# fastic.net
KiCad netlist of a schematic drawn in Altium Designer
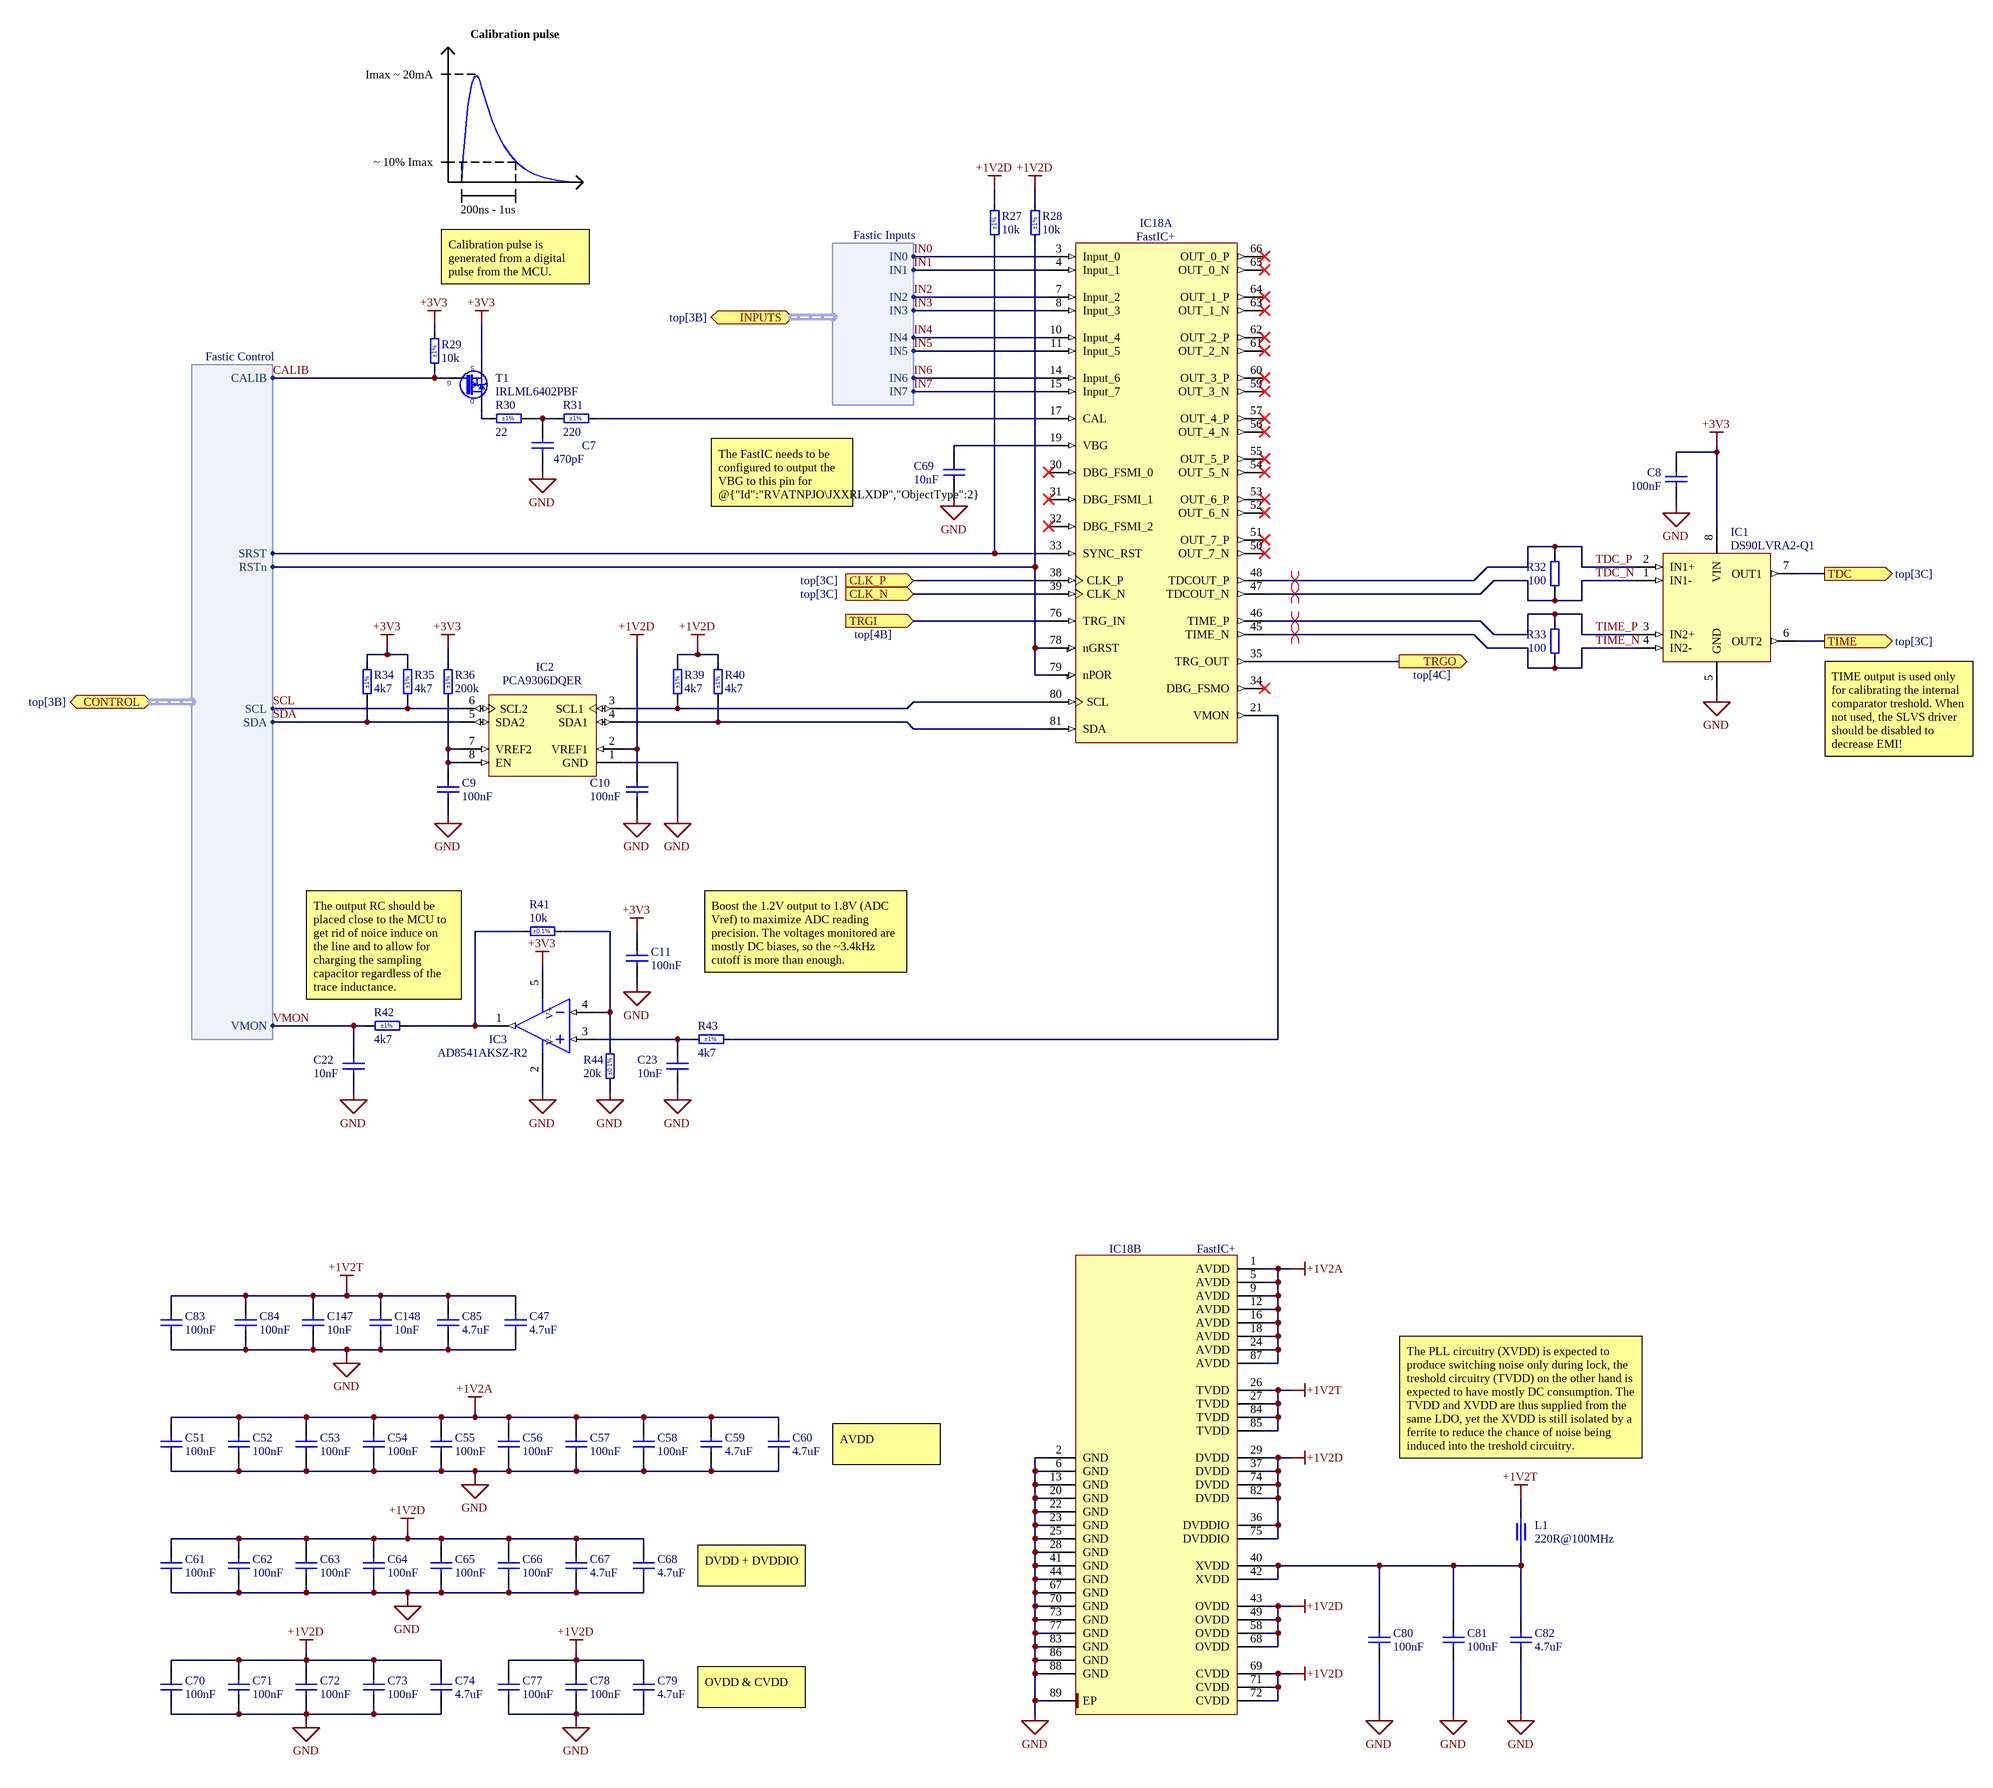
[diagram p0: fastic.SchDoc]

(export (version "E")
  (design (tool "Eeschema 10.0.6"))
  (components
    (comp (ref "C7")
      (value "470pF")
      (footprint "CAPC1005X55N")
      (description "Non-polarised capacitor")
      (fields
        (field (name "PART NUMBER") "CC0402_470PF_50V_10%_X7R")
        (field (name "VOLTAGE") "50V")
        (field (name "AUTHOR") "CERN DEM JLC")
      )
      (libsource (lib "Capacitors") (part "Capacitor - non polarized"))
    )
    (comp (ref "C8")
      (value "100nF")
      (footprint "CAPC1005X55N")
      (description "Non-polarised capacitor")
      (fields
        (field (name "PART NUMBER") "CC0402_100NF_16V_10%_X7R")
        (field (name "VOLTAGE") "16V")
        (field (name "AUTHOR") "CERN DEM JLC")
      )
      (libsource (lib "Capacitors") (part "Capacitor - non polarized"))
    )
    (comp (ref "C9")
      (value "100nF")
      (footprint "CAPC1005X55N")
      (description "Non-polarised capacitor")
      (fields
        (field (name "PART NUMBER") "CC0402_100NF_16V_10%_X7R")
        (field (name "VOLTAGE") "16V")
        (field (name "AUTHOR") "CERN DEM JLC")
      )
      (libsource (lib "Capacitors") (part "Capacitor - non polarized"))
    )
    (comp (ref "C10")
      (value "100nF")
      (footprint "CAPC1005X55N")
      (description "Non-polarised capacitor")
      (fields
        (field (name "PART NUMBER") "CC0402_100NF_16V_10%_X7R")
        (field (name "VOLTAGE") "16V")
        (field (name "AUTHOR") "CERN DEM JLC")
      )
      (libsource (lib "Capacitors") (part "Capacitor - non polarized"))
    )
    (comp (ref "C11")
      (value "100nF")
      (footprint "CAPC1005X55N")
      (description "Non-polarised capacitor")
      (fields
        (field (name "PART NUMBER") "CC0402_100NF_16V_10%_X7R")
        (field (name "VOLTAGE") "16V")
        (field (name "AUTHOR") "CERN DEM JLC")
      )
      (libsource (lib "Capacitors") (part "Capacitor - non polarized"))
    )
    (comp (ref "C22")
      (value "10nF")
      (footprint "CAPC1005X55N")
      (description "Non-polarised capacitor")
      (fields
        (field (name "PART NUMBER") "CC0402_10NF_50V_10%_X7R")
        (field (name "VOLTAGE") "50V")
        (field (name "AUTHOR") "CERN DEM MR")
      )
      (libsource (lib "Capacitors") (part "Capacitor - non polarized"))
    )
    (comp (ref "C23")
      (value "10nF")
      (footprint "CAPC1005X55N")
      (description "Non-polarised capacitor")
      (fields
        (field (name "PART NUMBER") "CC0402_10NF_50V_10%_X7R")
        (field (name "VOLTAGE") "50V")
        (field (name "AUTHOR") "CERN DEM MR")
      )
      (libsource (lib "Capacitors") (part "Capacitor - non polarized"))
    )
    (comp (ref "C47")
      (value "4.7uF")
      (footprint "CAPC1608X87N")
      (description "Non-polarised capacitor")
      (fields
        (field (name "PART NUMBER") "CC0603_4.7UF_6.3V_10%_X5R")
        (field (name "VOLTAGE") "6.3V")
        (field (name "AUTHOR") "CERN DEM JLC")
      )
      (libsource (lib "Capacitors") (part "Capacitor - non polarized"))
    )
    (comp (ref "C51")
      (value "100nF")
      (footprint "CAPC1005X55N")
      (description "Non-polarised capacitor")
      (fields
        (field (name "PART NUMBER") "CC0402_100NF_16V_10%_X7R")
        (field (name "VOLTAGE") "16V")
        (field (name "AUTHOR") "CERN DEM JLC")
      )
      (libsource (lib "Capacitors") (part "Capacitor - non polarized"))
    )
    (comp (ref "C52")
      (value "100nF")
      (footprint "CAPC1005X55N")
      (description "Non-polarised capacitor")
      (fields
        (field (name "PART NUMBER") "CC0402_100NF_16V_10%_X7R")
        (field (name "VOLTAGE") "16V")
        (field (name "AUTHOR") "CERN DEM JLC")
      )
      (libsource (lib "Capacitors") (part "Capacitor - non polarized"))
    )
    (comp (ref "C53")
      (value "100nF")
      (footprint "CAPC1005X55N")
      (description "Non-polarised capacitor")
      (fields
        (field (name "PART NUMBER") "CC0402_100NF_16V_10%_X7R")
        (field (name "VOLTAGE") "16V")
        (field (name "AUTHOR") "CERN DEM JLC")
      )
      (libsource (lib "Capacitors") (part "Capacitor - non polarized"))
    )
    (comp (ref "C54")
      (value "100nF")
      (footprint "CAPC1005X55N")
      (description "Non-polarised capacitor")
      (fields
        (field (name "PART NUMBER") "CC0402_100NF_16V_10%_X7R")
        (field (name "VOLTAGE") "16V")
        (field (name "AUTHOR") "CERN DEM JLC")
      )
      (libsource (lib "Capacitors") (part "Capacitor - non polarized"))
    )
    (comp (ref "C55")
      (value "100nF")
      (footprint "CAPC1005X55N")
      (description "Non-polarised capacitor")
      (fields
        (field (name "PART NUMBER") "CC0402_100NF_16V_10%_X7R")
        (field (name "VOLTAGE") "16V")
        (field (name "AUTHOR") "CERN DEM JLC")
      )
      (libsource (lib "Capacitors") (part "Capacitor - non polarized"))
    )
    (comp (ref "C56")
      (value "100nF")
      (footprint "CAPC1005X55N")
      (description "Non-polarised capacitor")
      (fields
        (field (name "PART NUMBER") "CC0402_100NF_16V_10%_X7R")
        (field (name "VOLTAGE") "16V")
        (field (name "AUTHOR") "CERN DEM JLC")
      )
      (libsource (lib "Capacitors") (part "Capacitor - non polarized"))
    )
    (comp (ref "C57")
      (value "100nF")
      (footprint "CAPC1005X55N")
      (description "Non-polarised capacitor")
      (fields
        (field (name "PART NUMBER") "CC0402_100NF_16V_10%_X7R")
        (field (name "VOLTAGE") "16V")
        (field (name "AUTHOR") "CERN DEM JLC")
      )
      (libsource (lib "Capacitors") (part "Capacitor - non polarized"))
    )
    (comp (ref "C58")
      (value "100nF")
      (footprint "CAPC1005X55N")
      (description "Non-polarised capacitor")
      (fields
        (field (name "PART NUMBER") "CC0402_100NF_16V_10%_X7R")
        (field (name "VOLTAGE") "16V")
        (field (name "AUTHOR") "CERN DEM JLC")
      )
      (libsource (lib "Capacitors") (part "Capacitor - non polarized"))
    )
    (comp (ref "C59")
      (value "4.7uF")
      (footprint "CAPC1608X87N")
      (description "Non-polarised capacitor")
      (fields
        (field (name "PART NUMBER") "CC0603_4.7UF_6.3V_10%_X5R")
        (field (name "VOLTAGE") "6.3V")
        (field (name "AUTHOR") "CERN DEM JLC")
      )
      (libsource (lib "Capacitors") (part "Capacitor - non polarized"))
    )
    (comp (ref "C60")
      (value "4.7uF")
      (footprint "CAPC1608X87N")
      (description "Non-polarised capacitor")
      (fields
        (field (name "PART NUMBER") "CC0603_4.7UF_6.3V_10%_X5R")
        (field (name "VOLTAGE") "6.3V")
        (field (name "AUTHOR") "CERN DEM JLC")
      )
      (libsource (lib "Capacitors") (part "Capacitor - non polarized"))
    )
    (comp (ref "C61")
      (value "100nF")
      (footprint "CAPC1005X55N")
      (description "Non-polarised capacitor")
      (fields
        (field (name "PART NUMBER") "CC0402_100NF_16V_10%_X7R")
        (field (name "VOLTAGE") "16V")
        (field (name "AUTHOR") "CERN DEM JLC")
      )
      (libsource (lib "Capacitors") (part "Capacitor - non polarized"))
    )
    (comp (ref "C62")
      (value "100nF")
      (footprint "CAPC1005X55N")
      (description "Non-polarised capacitor")
      (fields
        (field (name "PART NUMBER") "CC0402_100NF_16V_10%_X7R")
        (field (name "VOLTAGE") "16V")
        (field (name "AUTHOR") "CERN DEM JLC")
      )
      (libsource (lib "Capacitors") (part "Capacitor - non polarized"))
    )
    (comp (ref "C63")
      (value "100nF")
      (footprint "CAPC1005X55N")
      (description "Non-polarised capacitor")
      (fields
        (field (name "PART NUMBER") "CC0402_100NF_16V_10%_X7R")
        (field (name "VOLTAGE") "16V")
        (field (name "AUTHOR") "CERN DEM JLC")
      )
      (libsource (lib "Capacitors") (part "Capacitor - non polarized"))
    )
    (comp (ref "C64")
      (value "100nF")
      (footprint "CAPC1005X55N")
      (description "Non-polarised capacitor")
      (fields
        (field (name "PART NUMBER") "CC0402_100NF_16V_10%_X7R")
        (field (name "VOLTAGE") "16V")
        (field (name "AUTHOR") "CERN DEM JLC")
      )
      (libsource (lib "Capacitors") (part "Capacitor - non polarized"))
    )
    (comp (ref "C65")
      (value "100nF")
      (footprint "CAPC1005X55N")
      (description "Non-polarised capacitor")
      (fields
        (field (name "PART NUMBER") "CC0402_100NF_16V_10%_X7R")
        (field (name "VOLTAGE") "16V")
        (field (name "AUTHOR") "CERN DEM JLC")
      )
      (libsource (lib "Capacitors") (part "Capacitor - non polarized"))
    )
    (comp (ref "C66")
      (value "100nF")
      (footprint "CAPC1005X55N")
      (description "Non-polarised capacitor")
      (fields
        (field (name "PART NUMBER") "CC0402_100NF_16V_10%_X7R")
        (field (name "VOLTAGE") "16V")
        (field (name "AUTHOR") "CERN DEM JLC")
      )
      (libsource (lib "Capacitors") (part "Capacitor - non polarized"))
    )
    (comp (ref "C67")
      (value "4.7uF")
      (footprint "CAPC1608X87N")
      (description "Non-polarised capacitor")
      (fields
        (field (name "PART NUMBER") "CC0603_4.7UF_6.3V_10%_X5R")
        (field (name "VOLTAGE") "6.3V")
        (field (name "AUTHOR") "CERN DEM JLC")
      )
      (libsource (lib "Capacitors") (part "Capacitor - non polarized"))
    )
    (comp (ref "C68")
      (value "4.7uF")
      (footprint "CAPC1608X87N")
      (description "Non-polarised capacitor")
      (fields
        (field (name "PART NUMBER") "CC0603_4.7UF_6.3V_10%_X5R")
        (field (name "VOLTAGE") "6.3V")
        (field (name "AUTHOR") "CERN DEM JLC")
      )
      (libsource (lib "Capacitors") (part "Capacitor - non polarized"))
    )
    (comp (ref "C69")
      (value "10nF")
      (footprint "CAPC1005X55N")
      (description "Non-polarised capacitor")
      (fields
        (field (name "PART NUMBER") "CC0402_10NF_50V_10%_X7R")
        (field (name "VOLTAGE") "50V")
        (field (name "AUTHOR") "CERN DEM MR")
      )
      (libsource (lib "Capacitors") (part "Capacitor - non polarized"))
    )
    (comp (ref "C70")
      (value "100nF")
      (footprint "CAPC1005X55N")
      (description "Non-polarised capacitor")
      (fields
        (field (name "PART NUMBER") "CC0402_100NF_16V_10%_X7R")
        (field (name "VOLTAGE") "16V")
        (field (name "AUTHOR") "CERN DEM JLC")
      )
      (libsource (lib "Capacitors") (part "Capacitor - non polarized"))
    )
    (comp (ref "C71")
      (value "100nF")
      (footprint "CAPC1005X55N")
      (description "Non-polarised capacitor")
      (fields
        (field (name "PART NUMBER") "CC0402_100NF_16V_10%_X7R")
        (field (name "VOLTAGE") "16V")
        (field (name "AUTHOR") "CERN DEM JLC")
      )
      (libsource (lib "Capacitors") (part "Capacitor - non polarized"))
    )
    (comp (ref "C72")
      (value "100nF")
      (footprint "CAPC1005X55N")
      (description "Non-polarised capacitor")
      (fields
        (field (name "PART NUMBER") "CC0402_100NF_16V_10%_X7R")
        (field (name "VOLTAGE") "16V")
        (field (name "AUTHOR") "CERN DEM JLC")
      )
      (libsource (lib "Capacitors") (part "Capacitor - non polarized"))
    )
    (comp (ref "C73")
      (value "100nF")
      (footprint "CAPC1005X55N")
      (description "Non-polarised capacitor")
      (fields
        (field (name "PART NUMBER") "CC0402_100NF_16V_10%_X7R")
        (field (name "VOLTAGE") "16V")
        (field (name "AUTHOR") "CERN DEM JLC")
      )
      (libsource (lib "Capacitors") (part "Capacitor - non polarized"))
    )
    (comp (ref "C74")
      (value "4.7uF")
      (footprint "CAPC1608X87N")
      (description "Non-polarised capacitor")
      (fields
        (field (name "PART NUMBER") "CC0603_4.7UF_6.3V_10%_X5R")
        (field (name "VOLTAGE") "6.3V")
        (field (name "AUTHOR") "CERN DEM JLC")
      )
      (libsource (lib "Capacitors") (part "Capacitor - non polarized"))
    )
    (comp (ref "C77")
      (value "100nF")
      (footprint "CAPC1005X55N")
      (description "Non-polarised capacitor")
      (fields
        (field (name "PART NUMBER") "CC0402_100NF_16V_10%_X7R")
        (field (name "VOLTAGE") "16V")
        (field (name "AUTHOR") "CERN DEM JLC")
      )
      (libsource (lib "Capacitors") (part "Capacitor - non polarized"))
    )
    (comp (ref "C78")
      (value "100nF")
      (footprint "CAPC1005X55N")
      (description "Non-polarised capacitor")
      (fields
        (field (name "PART NUMBER") "CC0402_100NF_16V_10%_X7R")
        (field (name "VOLTAGE") "16V")
        (field (name "AUTHOR") "CERN DEM JLC")
      )
      (libsource (lib "Capacitors") (part "Capacitor - non polarized"))
    )
    (comp (ref "C79")
      (value "4.7uF")
      (footprint "CAPC1608X87N")
      (description "Non-polarised capacitor")
      (fields
        (field (name "PART NUMBER") "CC0603_4.7UF_6.3V_10%_X5R")
        (field (name "VOLTAGE") "6.3V")
        (field (name "AUTHOR") "CERN DEM JLC")
      )
      (libsource (lib "Capacitors") (part "Capacitor - non polarized"))
    )
    (comp (ref "C80")
      (value "100nF")
      (footprint "CAPC1005X55N")
      (description "Non-polarised capacitor")
      (fields
        (field (name "PART NUMBER") "CC0402_100NF_16V_10%_X7R")
        (field (name "VOLTAGE") "16V")
        (field (name "AUTHOR") "CERN DEM JLC")
      )
      (libsource (lib "Capacitors") (part "Capacitor - non polarized"))
    )
    (comp (ref "C81")
      (value "100nF")
      (footprint "CAPC1005X55N")
      (description "Non-polarised capacitor")
      (fields
        (field (name "PART NUMBER") "CC0402_100NF_16V_10%_X7R")
        (field (name "VOLTAGE") "16V")
        (field (name "AUTHOR") "CERN DEM JLC")
      )
      (libsource (lib "Capacitors") (part "Capacitor - non polarized"))
    )
    (comp (ref "C82")
      (value "4.7uF")
      (footprint "CAPC1608X87N")
      (description "Non-polarised capacitor")
      (fields
        (field (name "PART NUMBER") "CC0603_4.7UF_6.3V_10%_X5R")
        (field (name "VOLTAGE") "6.3V")
        (field (name "AUTHOR") "CERN DEM JLC")
      )
      (libsource (lib "Capacitors") (part "Capacitor - non polarized"))
    )
    (comp (ref "C83")
      (value "100nF")
      (footprint "CAPC1005X55N")
      (description "Non-polarised capacitor")
      (fields
        (field (name "PART NUMBER") "CC0402_100NF_16V_10%_X7R")
        (field (name "VOLTAGE") "16V")
        (field (name "AUTHOR") "CERN DEM JLC")
      )
      (libsource (lib "Capacitors") (part "Capacitor - non polarized"))
    )
    (comp (ref "C84")
      (value "100nF")
      (footprint "CAPC1005X55N")
      (description "Non-polarised capacitor")
      (fields
        (field (name "PART NUMBER") "CC0402_100NF_16V_10%_X7R")
        (field (name "VOLTAGE") "16V")
        (field (name "AUTHOR") "CERN DEM JLC")
      )
      (libsource (lib "Capacitors") (part "Capacitor - non polarized"))
    )
    (comp (ref "C85")
      (value "4.7uF")
      (footprint "CAPC1608X87N")
      (description "Non-polarised capacitor")
      (fields
        (field (name "PART NUMBER") "CC0603_4.7UF_6.3V_10%_X5R")
        (field (name "VOLTAGE") "6.3V")
        (field (name "AUTHOR") "CERN DEM JLC")
      )
      (libsource (lib "Capacitors") (part "Capacitor - non polarized"))
    )
    (comp (ref "C147")
      (value "10nF")
      (footprint "CAPC1005X55N")
      (description "Non-polarised capacitor")
      (fields
        (field (name "PART NUMBER") "CC0402_10NF_50V_10%_X7R")
        (field (name "VOLTAGE") "50V")
        (field (name "AUTHOR") "CERN DEM MR")
      )
      (libsource (lib "Capacitors") (part "Capacitor - non polarized"))
    )
    (comp (ref "C148")
      (value "10nF")
      (footprint "CAPC1005X55N")
      (description "Non-polarised capacitor")
      (fields
        (field (name "PART NUMBER") "CC0402_10NF_50V_10%_X7R")
        (field (name "VOLTAGE") "50V")
        (field (name "AUTHOR") "CERN DEM MR")
      )
      (libsource (lib "Capacitors") (part "Capacitor - non polarized"))
    )
    (comp (ref "IC1")
      (value "DS90LVRA2-Q1")
      (footprint "DS90LVRA2-Q1")
      (libsource (lib "fastic_readout") (part "DS90LVRA2-Q1"))
    )
    (comp (ref "IC2")
      (value "PCA9306DQER")
      (footprint "SON35P100X140X40-8N")
      (libsource (lib "fastic_readout") (part "PCA9306DQER"))
    )
    (comp (ref "IC3")
      (value "AD8541AKSZ-R2")
      (footprint "SOT65P210X110-5N")
      (description "Operational Amplifier")
      (fields
        (field (name "MANUFACTURER") "ANALOG DEVICES")
        (field (name "MANUFACTURER PART NUMBER") "AD8541AKS")
        (field (name "AUTHOR") "CERN DEM JLC")
      )
      (libsource (lib "ICs And Semiconductors") (part "Operational Amplifier Type7"))
    )
    (comp (ref "IC18")
      (value "FastIC+")
      (footprint "QFN40P1000X1000X85-89N-S760")
      (fields (field (name "MANUFACTURER") "CERN") (field (name "AUTHOR") "CERN DEM HF"))
      (libsource (lib "ICs And Semiconductors") (part "FastIC+"))
    )
    (comp (ref "L1")
      (value "220R@100MHz")
      (footprint "INDC1005X55N")
      (fields
        (field (name "PART NUMBER") "IND0402_MURATA_BLM15HB221SN1")
        (field (name "POWER") "250mA")
        (field (name "TOLERANCE") "±25%")
        (field (name "AUTHOR") "CERN DEM JLC")
      )
      (libsource (lib "Inductors & Transformers") (part "Ferrite Bead"))
    )
    (comp (ref "R27")
      (value "10k")
      (footprint "RESC1005X40N")
      (description "Resistor - 1%")
      (fields
        (field (name "TOLERANCE") "±1%")
        (field (name "PART NUMBER") "R0402_10K_1%_0.0625W_100PPM")
        (field (name "POWER") "0.0625W")
        (field (name "AUTHOR") "CERN DEM JLC")
      )
      (libsource (lib "Resistors") (part "Resistor - 1%"))
    )
    (comp (ref "R28")
      (value "10k")
      (footprint "RESC1005X40N")
      (description "Resistor - 1%")
      (fields
        (field (name "TOLERANCE") "±1%")
        (field (name "PART NUMBER") "R0402_10K_1%_0.0625W_100PPM")
        (field (name "POWER") "0.0625W")
        (field (name "AUTHOR") "CERN DEM JLC")
      )
      (libsource (lib "Resistors") (part "Resistor - 1%"))
    )
    (comp (ref "R29")
      (value "10k")
      (footprint "RESC1005X40N")
      (description "Resistor - 1%")
      (fields
        (field (name "TOLERANCE") "±1%")
        (field (name "PART NUMBER") "R0402_10K_1%_0.0625W_100PPM")
        (field (name "POWER") "0.0625W")
        (field (name "AUTHOR") "CERN DEM JLC")
      )
      (libsource (lib "Resistors") (part "Resistor - 1%"))
    )
    (comp (ref "R30")
      (value "22")
      (footprint "RESC1005X40N")
      (description "Resistor - 1%")
      (fields
        (field (name "TOLERANCE") "±1%")
        (field (name "PART NUMBER") "R0402_22R_1%_0.0625W_100PPM")
        (field (name "POWER") "0.0625W")
        (field (name "AUTHOR") "CERN DEM JLC")
      )
      (libsource (lib "Resistors") (part "Resistor - 1%"))
    )
    (comp (ref "R31")
      (value "220")
      (footprint "RESC1005X40N")
      (description "Resistor - 1%")
      (fields
        (field (name "TOLERANCE") "±1%")
        (field (name "PART NUMBER") "R0402_220R_1%_0.0625W_100PPM")
        (field (name "POWER") "0.0625W")
        (field (name "AUTHOR") "CERN DEM JLC")
      )
      (libsource (lib "Resistors") (part "Resistor - 1%"))
    )
    (comp (ref "R32")
      (value "100")
      (footprint "RESC1005X40N")
      (description "Resistor - 1%")
      (fields
        (field (name "PART NUMBER") "R0402_100R_1%_0.1W_100PPM")
        (field (name "POWER") "0.1W")
        (field (name "AUTHOR") "CERN DEM JLC")
      )
      (libsource (lib "Resistors") (part "Resistor - 1%"))
    )
    (comp (ref "R33")
      (value "100")
      (footprint "RESC1005X40N")
      (description "Resistor - 1%")
      (fields
        (field (name "PART NUMBER") "R0402_100R_1%_0.1W_100PPM")
        (field (name "POWER") "0.1W")
        (field (name "AUTHOR") "CERN DEM JLC")
      )
      (libsource (lib "Resistors") (part "Resistor - 1%"))
    )
    (comp (ref "R34")
      (value "4k7")
      (footprint "RESC1005X40N")
      (description "Resistor - 1%")
      (fields
        (field (name "TOLERANCE") "±1%")
        (field (name "PART NUMBER") "R0402_4K7_1%_0.0625W_100PPM")
        (field (name "POWER") "0.0625W")
        (field (name "AUTHOR") "CERN DEM JLC")
      )
      (libsource (lib "Resistors") (part "Resistor - 1%"))
    )
    (comp (ref "R35")
      (value "4k7")
      (footprint "RESC1005X40N")
      (description "Resistor - 1%")
      (fields
        (field (name "TOLERANCE") "±1%")
        (field (name "PART NUMBER") "R0402_4K7_1%_0.0625W_100PPM")
        (field (name "POWER") "0.0625W")
        (field (name "AUTHOR") "CERN DEM JLC")
      )
      (libsource (lib "Resistors") (part "Resistor - 1%"))
    )
    (comp (ref "R36")
      (value "200k")
      (footprint "RESC1005X40N")
      (description "Resistor - 1%")
      (fields
        (field (name "TOLERANCE") "±1%")
        (field (name "PART NUMBER") "R0402_200K_1%_0.0625W_100PPM")
        (field (name "POWER") "0.0625W")
        (field (name "AUTHOR") "CERN DEM JLC")
      )
      (libsource (lib "Resistors") (part "Resistor - 1%"))
    )
    (comp (ref "R39")
      (value "4k7")
      (footprint "RESC1005X40N")
      (description "Resistor - 1%")
      (fields
        (field (name "TOLERANCE") "±1%")
        (field (name "PART NUMBER") "R0402_4K7_1%_0.0625W_100PPM")
        (field (name "POWER") "0.0625W")
        (field (name "AUTHOR") "CERN DEM JLC")
      )
      (libsource (lib "Resistors") (part "Resistor - 1%"))
    )
    (comp (ref "R40")
      (value "4k7")
      (footprint "RESC1005X40N")
      (description "Resistor - 1%")
      (fields
        (field (name "TOLERANCE") "±1%")
        (field (name "PART NUMBER") "R0402_4K7_1%_0.0625W_100PPM")
        (field (name "POWER") "0.0625W")
        (field (name "AUTHOR") "CERN DEM JLC")
      )
      (libsource (lib "Resistors") (part "Resistor - 1%"))
    )
    (comp (ref "R41")
      (value "10k")
      (footprint "RESC1005X35N")
      (description "Resistor - 0.1%")
      (fields
        (field (name "TOLERANCE") "±0.1%")
        (field (name "PART NUMBER") "R0402_10K_0.1%_0.063W_25PPM")
        (field (name "POWER") "0.063W")
        (field (name "AUTHOR") "CERN DEM JMW")
      )
      (libsource (lib "Resistors") (part "Resistor - 0.1%"))
    )
    (comp (ref "R42")
      (value "4k7")
      (footprint "RESC1005X40N")
      (description "Resistor - 1%")
      (fields
        (field (name "TOLERANCE") "±1%")
        (field (name "PART NUMBER") "R0402_4K7_1%_0.0625W_100PPM")
        (field (name "POWER") "0.0625W")
        (field (name "AUTHOR") "CERN DEM JLC")
      )
      (libsource (lib "Resistors") (part "Resistor - 1%"))
    )
    (comp (ref "R43")
      (value "4k7")
      (footprint "RESC1005X40N")
      (description "Resistor - 1%")
      (fields
        (field (name "TOLERANCE") "±1%")
        (field (name "PART NUMBER") "R0402_4K7_1%_0.0625W_100PPM")
        (field (name "POWER") "0.0625W")
        (field (name "AUTHOR") "CERN DEM JLC")
      )
      (libsource (lib "Resistors") (part "Resistor - 1%"))
    )
    (comp (ref "R44")
      (value "20k")
      (footprint "RESC1005X40N")
      (description "Resistor - 0.1%")
      (fields
        (field (name "TOLERANCE") "±0.1%")
        (field (name "PART NUMBER") "R0402_20K_0.1%_0.063W_25PPM")
        (field (name "POWER") "0.063W")
        (field (name "AUTHOR") "CERN DEM BC")
      )
      (libsource (lib "Resistors") (part "Resistor - 0.1%"))
    )
    (comp (ref "T1")
      (value "IRLML6402PBF")
      (footprint "SOT95P237X112-3N")
      (description "P-CHANNEL MOSFET WITH ZENER DIODE")
      (fields
        (field (name "MANUFACTURER") "INTERNATIONAL RECTIFIER")
        (field (name "MANUFACTURER PART NUMBER") "IRLML6402")
        (field (name "AUTHOR") "CERN DEM JLC")
      )
      (libsource (lib "ICs And Semiconductors") (part "P-MOSFET-DZ 1G 2S 3D"))
    )
  )
  (nets
    (net (code "4") (name "+1V2A") (class "Default")
      (node (ref "C51") (pin "1") (pinfunction "1_1") (pintype "passive"))
      (node (ref "C52") (pin "1") (pinfunction "1_1") (pintype "passive"))
      (node (ref "C53") (pin "1") (pinfunction "1_1") (pintype "passive"))
      (node (ref "C54") (pin "1") (pinfunction "1_1") (pintype "passive"))
      (node (ref "C55") (pin "1") (pinfunction "1_1") (pintype "passive"))
      (node (ref "C56") (pin "1") (pinfunction "1_1") (pintype "passive"))
      (node (ref "C57") (pin "1") (pinfunction "1_1") (pintype "passive"))
      (node (ref "C58") (pin "1") (pinfunction "1_1") (pintype "passive"))
      (node (ref "C59") (pin "1") (pinfunction "1_1") (pintype "passive"))
      (node (ref "C60") (pin "1") (pinfunction "1_1") (pintype "passive"))
      (node (ref "IC18") (pin "1") (pinfunction "AVDD_1") (pintype "power_in"))
      (node (ref "IC18") (pin "12") (pinfunction "AVDD_12") (pintype "power_in"))
      (node (ref "IC18") (pin "16") (pinfunction "AVDD_16") (pintype "power_in"))
      (node (ref "IC18") (pin "18") (pinfunction "AVDD_18") (pintype "power_in"))
      (node (ref "IC18") (pin "24") (pinfunction "AVDD_24") (pintype "power_in"))
      (node (ref "IC18") (pin "5") (pinfunction "AVDD_5") (pintype "power_in"))
      (node (ref "IC18") (pin "87") (pinfunction "AVDD_87") (pintype "power_in"))
      (node (ref "IC18") (pin "9") (pinfunction "AVDD_9") (pintype "power_in"))
    )
    (net (code "5") (name "+1V2D") (class "Default")
      (node (ref "C10") (pin "1") (pinfunction "1_1") (pintype "passive"))
      (node (ref "C61") (pin "1") (pinfunction "1_1") (pintype "passive"))
      (node (ref "C62") (pin "1") (pinfunction "1_1") (pintype "passive"))
      (node (ref "C63") (pin "1") (pinfunction "1_1") (pintype "passive"))
      (node (ref "C64") (pin "1") (pinfunction "1_1") (pintype "passive"))
      (node (ref "C65") (pin "1") (pinfunction "1_1") (pintype "passive"))
      (node (ref "C66") (pin "1") (pinfunction "1_1") (pintype "passive"))
      (node (ref "C67") (pin "1") (pinfunction "1_1") (pintype "passive"))
      (node (ref "C68") (pin "1") (pinfunction "1_1") (pintype "passive"))
      (node (ref "C70") (pin "1") (pinfunction "1_1") (pintype "passive"))
      (node (ref "C71") (pin "1") (pinfunction "1_1") (pintype "passive"))
      (node (ref "C72") (pin "1") (pinfunction "1_1") (pintype "passive"))
      (node (ref "C73") (pin "1") (pinfunction "1_1") (pintype "passive"))
      (node (ref "C74") (pin "1") (pinfunction "1_1") (pintype "passive"))
      (node (ref "C77") (pin "1") (pinfunction "1_1") (pintype "passive"))
      (node (ref "C78") (pin "1") (pinfunction "1_1") (pintype "passive"))
      (node (ref "C79") (pin "1") (pinfunction "1_1") (pintype "passive"))
      (node (ref "IC18") (pin "29") (pinfunction "DVDD_29") (pintype "power_in"))
      (node (ref "IC18") (pin "36") (pinfunction "DVDDIO_36") (pintype "power_in"))
      (node (ref "IC18") (pin "37") (pinfunction "DVDD_37") (pintype "power_in"))
      (node (ref "IC18") (pin "43") (pinfunction "OVDD_43") (pintype "power_in"))
      (node (ref "IC18") (pin "49") (pinfunction "OVDD_49") (pintype "power_in"))
      (node (ref "IC18") (pin "58") (pinfunction "OVDD_58") (pintype "power_in"))
      (node (ref "IC18") (pin "68") (pinfunction "OVDD_68") (pintype "power_in"))
      (node (ref "IC18") (pin "69") (pinfunction "CVDD_69") (pintype "power_in"))
      (node (ref "IC18") (pin "71") (pinfunction "CVDD_71") (pintype "power_in"))
      (node (ref "IC18") (pin "72") (pinfunction "CVDD_72") (pintype "power_in"))
      (node (ref "IC18") (pin "74") (pinfunction "DVDD_74") (pintype "power_in"))
      (node (ref "IC18") (pin "75") (pinfunction "DVDDIO_75") (pintype "power_in"))
      (node (ref "IC18") (pin "82") (pinfunction "DVDD_82") (pintype "power_in"))
      (node (ref "IC2") (pin "2") (pinfunction "VREF1_2") (pintype "input"))
      (node (ref "R27") (pin "2") (pinfunction "2_2") (pintype "passive"))
      (node (ref "R28") (pin "2") (pinfunction "2_2") (pintype "passive"))
      (node (ref "R39") (pin "2") (pinfunction "2_2") (pintype "passive"))
      (node (ref "R40") (pin "2") (pinfunction "2_2") (pintype "passive"))
    )
    (net (code "6") (name "+1V2T") (class "Default")
      (node (ref "C147") (pin "1") (pinfunction "1_1") (pintype "passive"))
      (node (ref "C148") (pin "1") (pinfunction "1_1") (pintype "passive"))
      (node (ref "C47") (pin "1") (pinfunction "1_1") (pintype "passive"))
      (node (ref "C83") (pin "1") (pinfunction "1_1") (pintype "passive"))
      (node (ref "C84") (pin "1") (pinfunction "1_1") (pintype "passive"))
      (node (ref "C85") (pin "1") (pinfunction "1_1") (pintype "passive"))
      (node (ref "IC18") (pin "26") (pinfunction "TVDD_26") (pintype "power_in"))
      (node (ref "IC18") (pin "27") (pinfunction "TVDD_27") (pintype "power_in"))
      (node (ref "IC18") (pin "84") (pinfunction "TVDD_84") (pintype "power_in"))
      (node (ref "IC18") (pin "85") (pinfunction "TVDD_85") (pintype "power_in"))
      (node (ref "L1") (pin "2") (pinfunction "2_2") (pintype "passive"))
    )
    (net (code "7") (name "+3V3") (class "Default")
      (node (ref "C11") (pin "2") (pinfunction "2_2") (pintype "passive"))
      (node (ref "C8") (pin "1") (pinfunction "1_1") (pintype "passive"))
      (node (ref "IC1") (pin "8") (pinfunction "VIN_8") (pintype "power_in"))
      (node (ref "IC3") (pin "5") (pinfunction "V+_5") (pintype "power_in"))
      (node (ref "R29") (pin "2") (pinfunction "2_2") (pintype "passive"))
      (node (ref "R34") (pin "2") (pinfunction "2_2") (pintype "passive"))
      (node (ref "R35") (pin "2") (pinfunction "2_2") (pintype "passive"))
      (node (ref "R36") (pin "2") (pinfunction "2_2") (pintype "passive"))
      (node (ref "T1") (pin "2") (pinfunction "S_2") (pintype "passive"))
    )
    (net (code "8") (name "/CALIB") (class "Default")
      (node (ref "R29") (pin "1") (pinfunction "1_1") (pintype "passive"))
      (node (ref "T1") (pin "1") (pinfunction "G_1") (pintype "passive"))
    )
    (net (code "9") (name "/CLK_N") (class "Default")
      (node (ref "IC18") (pin "39") (pinfunction "CLK_N_39") (pintype "input"))
    )
    (net (code "10") (name "/CLK_P") (class "Default")
      (node (ref "IC18") (pin "38") (pinfunction "CLK_P_38") (pintype "input"))
    )
    (net (code "11") (name "/IN0") (class "Default")
      (node (ref "IC18") (pin "3") (pinfunction "Input_0_3") (pintype "input"))
    )
    (net (code "12") (name "/IN1") (class "Default")
      (node (ref "IC18") (pin "4") (pinfunction "Input_1_4") (pintype "input"))
    )
    (net (code "13") (name "/IN2") (class "Default")
      (node (ref "IC18") (pin "7") (pinfunction "Input_2_7") (pintype "input"))
    )
    (net (code "14") (name "/IN3") (class "Default")
      (node (ref "IC18") (pin "8") (pinfunction "Input_3_8") (pintype "input"))
    )
    (net (code "15") (name "/IN4") (class "Default")
      (node (ref "IC18") (pin "10") (pinfunction "Input_4_10") (pintype "input"))
    )
    (net (code "16") (name "/IN5") (class "Default")
      (node (ref "IC18") (pin "11") (pinfunction "Input_5_11") (pintype "input"))
    )
    (net (code "17") (name "/IN6") (class "Default")
      (node (ref "IC18") (pin "14") (pinfunction "Input_6_14") (pintype "input"))
    )
    (net (code "18") (name "/IN7") (class "Default")
      (node (ref "IC18") (pin "15") (pinfunction "Input_7_15") (pintype "input"))
    )
    (net (code "19") (name "/SCL") (class "Default")
      (node (ref "IC2") (pin "6") (pinfunction "SCL2_6") (pintype "bidirectional"))
      (node (ref "R35") (pin "1") (pinfunction "1_1") (pintype "passive"))
    )
    (net (code "20") (name "/SDA") (class "Default")
      (node (ref "IC2") (pin "5") (pinfunction "SDA2_5") (pintype "bidirectional"))
      (node (ref "R34") (pin "1") (pinfunction "1_1") (pintype "passive"))
    )
    (net (code "21") (name "/TDC") (class "Default")
      (node (ref "IC1") (pin "7") (pinfunction "OUT1_7") (pintype "output"))
    )
    (net (code "22") (name "/TDC_N") (class "Default")
      (node (ref "IC1") (pin "1") (pinfunction "IN1-_1") (pintype "input"))
      (node (ref "IC18") (pin "47") (pinfunction "TDCOUT_N_47") (pintype "output"))
      (node (ref "R32") (pin "2") (pinfunction "2_2") (pintype "passive"))
    )
    (net (code "23") (name "/TDC_P") (class "Default")
      (node (ref "IC1") (pin "2") (pinfunction "IN1+_2") (pintype "input"))
      (node (ref "IC18") (pin "48") (pinfunction "TDCOUT_P_48") (pintype "output"))
      (node (ref "R32") (pin "1") (pinfunction "1_1") (pintype "passive"))
    )
    (net (code "24") (name "/TIME") (class "Default")
      (node (ref "IC1") (pin "6") (pinfunction "OUT2_6") (pintype "output"))
    )
    (net (code "25") (name "/TIME_N") (class "Default")
      (node (ref "IC1") (pin "4") (pinfunction "IN2-_4") (pintype "input"))
      (node (ref "IC18") (pin "45") (pinfunction "TIME_N_45") (pintype "output"))
      (node (ref "R33") (pin "2") (pinfunction "2_2") (pintype "passive"))
    )
    (net (code "26") (name "/TIME_P") (class "Default")
      (node (ref "IC1") (pin "3") (pinfunction "IN2+_3") (pintype "input"))
      (node (ref "IC18") (pin "46") (pinfunction "TIME_P_46") (pintype "output"))
      (node (ref "R33") (pin "1") (pinfunction "1_1") (pintype "passive"))
    )
    (net (code "27") (name "/TRGI") (class "Default")
      (node (ref "IC18") (pin "76") (pinfunction "TRG_IN_76") (pintype "input"))
    )
    (net (code "28") (name "/TRGO") (class "Default")
      (node (ref "IC18") (pin "35") (pinfunction "TRG_OUT_35") (pintype "output"))
    )
    (net (code "29") (name "/VMON") (class "Default")
      (node (ref "C22") (pin "2") (pinfunction "2_2") (pintype "passive"))
      (node (ref "R42") (pin "2") (pinfunction "2_2") (pintype "passive"))
    )
    (net (code "32") (name "GND") (class "Default")
      (node (ref "C10") (pin "2") (pinfunction "2_2") (pintype "passive"))
      (node (ref "C11") (pin "1") (pinfunction "1_1") (pintype "passive"))
      (node (ref "C147") (pin "2") (pinfunction "2_2") (pintype "passive"))
      (node (ref "C148") (pin "2") (pinfunction "2_2") (pintype "passive"))
      (node (ref "C22") (pin "1") (pinfunction "1_1") (pintype "passive"))
      (node (ref "C23") (pin "1") (pinfunction "1_1") (pintype "passive"))
      (node (ref "C47") (pin "2") (pinfunction "2_2") (pintype "passive"))
      (node (ref "C51") (pin "2") (pinfunction "2_2") (pintype "passive"))
      (node (ref "C52") (pin "2") (pinfunction "2_2") (pintype "passive"))
      (node (ref "C53") (pin "2") (pinfunction "2_2") (pintype "passive"))
      (node (ref "C54") (pin "2") (pinfunction "2_2") (pintype "passive"))
      (node (ref "C55") (pin "2") (pinfunction "2_2") (pintype "passive"))
      (node (ref "C56") (pin "2") (pinfunction "2_2") (pintype "passive"))
      (node (ref "C57") (pin "2") (pinfunction "2_2") (pintype "passive"))
      (node (ref "C58") (pin "2") (pinfunction "2_2") (pintype "passive"))
      (node (ref "C59") (pin "2") (pinfunction "2_2") (pintype "passive"))
      (node (ref "C60") (pin "2") (pinfunction "2_2") (pintype "passive"))
      (node (ref "C61") (pin "2") (pinfunction "2_2") (pintype "passive"))
      (node (ref "C62") (pin "2") (pinfunction "2_2") (pintype "passive"))
      (node (ref "C63") (pin "2") (pinfunction "2_2") (pintype "passive"))
      (node (ref "C64") (pin "2") (pinfunction "2_2") (pintype "passive"))
      (node (ref "C65") (pin "2") (pinfunction "2_2") (pintype "passive"))
      (node (ref "C66") (pin "2") (pinfunction "2_2") (pintype "passive"))
      (node (ref "C67") (pin "2") (pinfunction "2_2") (pintype "passive"))
      (node (ref "C68") (pin "2") (pinfunction "2_2") (pintype "passive"))
      (node (ref "C69") (pin "2") (pinfunction "2_2") (pintype "passive"))
      (node (ref "C7") (pin "1") (pinfunction "1_1") (pintype "passive"))
      (node (ref "C70") (pin "2") (pinfunction "2_2") (pintype "passive"))
      (node (ref "C71") (pin "2") (pinfunction "2_2") (pintype "passive"))
      (node (ref "C72") (pin "2") (pinfunction "2_2") (pintype "passive"))
      (node (ref "C73") (pin "2") (pinfunction "2_2") (pintype "passive"))
      (node (ref "C74") (pin "2") (pinfunction "2_2") (pintype "passive"))
      (node (ref "C77") (pin "2") (pinfunction "2_2") (pintype "passive"))
      (node (ref "C78") (pin "2") (pinfunction "2_2") (pintype "passive"))
      (node (ref "C79") (pin "2") (pinfunction "2_2") (pintype "passive"))
      (node (ref "C8") (pin "2") (pinfunction "2_2") (pintype "passive"))
      (node (ref "C80") (pin "2") (pinfunction "2_2") (pintype "passive"))
      (node (ref "C81") (pin "2") (pinfunction "2_2") (pintype "passive"))
      (node (ref "C82") (pin "2") (pinfunction "2_2") (pintype "passive"))
      (node (ref "C83") (pin "2") (pinfunction "2_2") (pintype "passive"))
      (node (ref "C84") (pin "2") (pinfunction "2_2") (pintype "passive"))
      (node (ref "C85") (pin "2") (pinfunction "2_2") (pintype "passive"))
      (node (ref "C9") (pin "2") (pinfunction "2_2") (pintype "passive"))
      (node (ref "IC1") (pin "5") (pinfunction "GND_5") (pintype "power_in"))
      (node (ref "IC18") (pin "13") (pinfunction "GND_13") (pintype "power_in"))
      (node (ref "IC18") (pin "2") (pinfunction "GND_2") (pintype "power_in"))
      (node (ref "IC18") (pin "20") (pinfunction "GND_20") (pintype "power_in"))
      (node (ref "IC18") (pin "22") (pinfunction "GND_22") (pintype "power_in"))
      (node (ref "IC18") (pin "23") (pinfunction "GND_23") (pintype "power_in"))
      (node (ref "IC18") (pin "25") (pinfunction "GND_25") (pintype "power_in"))
      (node (ref "IC18") (pin "28") (pinfunction "GND_28") (pintype "power_in"))
      (node (ref "IC18") (pin "41") (pinfunction "GND_41") (pintype "power_in"))
      (node (ref "IC18") (pin "44") (pinfunction "GND_44") (pintype "power_in"))
      (node (ref "IC18") (pin "6") (pinfunction "GND_6") (pintype "power_in"))
      (node (ref "IC18") (pin "67") (pinfunction "GND_67") (pintype "power_in"))
      (node (ref "IC18") (pin "70") (pinfunction "GND_70") (pintype "power_in"))
      (node (ref "IC18") (pin "73") (pinfunction "GND_73") (pintype "power_in"))
      (node (ref "IC18") (pin "77") (pinfunction "GND_77") (pintype "power_in"))
      (node (ref "IC18") (pin "83") (pinfunction "GND_83") (pintype "power_in"))
      (node (ref "IC18") (pin "86") (pinfunction "GND_86") (pintype "power_in"))
      (node (ref "IC18") (pin "88") (pinfunction "GND_88") (pintype "power_in"))
      (node (ref "IC18") (pin "89") (pinfunction "EP_89") (pintype "power_in"))
      (node (ref "IC2") (pin "1") (pinfunction "GND_1") (pintype "power_in"))
      (node (ref "IC3") (pin "2") (pinfunction "V-_2") (pintype "power_in"))
      (node (ref "R44") (pin "1") (pinfunction "1_1") (pintype "passive"))
    )
    (net (code "33") (name "Net-(C7-Pad2)") (class "Default")
      (node (ref "C7") (pin "2") (pinfunction "2_2") (pintype "passive"))
      (node (ref "R30") (pin "2") (pinfunction "2_2") (pintype "passive"))
      (node (ref "R31") (pin "1") (pinfunction "1_1") (pintype "passive"))
    )
    (net (code "34") (name "Net-(C80-Pad1)") (class "Default")
      (node (ref "C80") (pin "1") (pinfunction "1_1") (pintype "passive"))
      (node (ref "C81") (pin "1") (pinfunction "1_1") (pintype "passive"))
      (node (ref "C82") (pin "1") (pinfunction "1_1") (pintype "passive"))
      (node (ref "IC18") (pin "40") (pinfunction "XVDD_40") (pintype "power_in"))
      (node (ref "IC18") (pin "42") (pinfunction "XVDD_42") (pintype "power_in"))
      (node (ref "L1") (pin "1") (pinfunction "1_1") (pintype "passive"))
    )
    (net (code "35") (name "Net-(IC2-EN)") (class "Default")
      (node (ref "C9") (pin "1") (pinfunction "1_1") (pintype "passive"))
      (node (ref "IC2") (pin "7") (pinfunction "VREF2_7") (pintype "input"))
      (node (ref "IC2") (pin "8") (pinfunction "EN_8") (pintype "input"))
      (node (ref "R36") (pin "1") (pinfunction "1_1") (pintype "passive"))
    )
    (net (code "36") (name "Net-(IC3-IN+)") (class "Default")
      (node (ref "C23") (pin "2") (pinfunction "2_2") (pintype "passive"))
      (node (ref "IC3") (pin "3") (pinfunction "IN+_3") (pintype "input"))
      (node (ref "R43") (pin "2") (pinfunction "2_2") (pintype "passive"))
    )
    (net (code "37") (name "Net-(IC3-IN-)") (class "Default")
      (node (ref "IC3") (pin "4") (pinfunction "IN-_4") (pintype "input"))
      (node (ref "R41") (pin "2") (pinfunction "2_2") (pintype "passive"))
      (node (ref "R44") (pin "2") (pinfunction "2_2") (pintype "passive"))
    )
    (net (code "38") (name "Net-(IC3-OUT)") (class "Default")
      (node (ref "IC3") (pin "1") (pinfunction "OUT_1") (pintype "output"))
      (node (ref "R41") (pin "1") (pinfunction "1_1") (pintype "passive"))
      (node (ref "R42") (pin "1") (pinfunction "1_1") (pintype "passive"))
    )
    (net (code "39") (name "Net-(IC18A-CAL)") (class "Default")
      (node (ref "IC18") (pin "17") (pinfunction "CAL_17") (pintype "input"))
      (node (ref "R31") (pin "2") (pinfunction "2_2") (pintype "passive"))
    )
    (net (code "40") (name "Net-(IC18A-SCL)") (class "Default")
      (node (ref "IC18") (pin "80") (pinfunction "SCL_80") (pintype "input"))
      (node (ref "IC2") (pin "3") (pinfunction "SCL1_3") (pintype "bidirectional"))
      (node (ref "R39") (pin "1") (pinfunction "1_1") (pintype "passive"))
    )
    (net (code "41") (name "Net-(IC18A-SDA)") (class "Default")
      (node (ref "IC18") (pin "81") (pinfunction "SDA_81") (pintype "input"))
      (node (ref "IC2") (pin "4") (pinfunction "SDA1_4") (pintype "bidirectional"))
      (node (ref "R40") (pin "1") (pinfunction "1_1") (pintype "passive"))
    )
    (net (code "42") (name "Net-(IC18A-SYNC_RST)") (class "Default")
      (node (ref "IC18") (pin "33") (pinfunction "SYNC_RST_33") (pintype "input"))
      (node (ref "R27") (pin "1") (pinfunction "1_1") (pintype "passive"))
    )
    (net (code "43") (name "Net-(IC18A-VBG)") (class "Default")
      (node (ref "C69") (pin "1") (pinfunction "1_1") (pintype "passive"))
      (node (ref "IC18") (pin "19") (pinfunction "VBG_19") (pintype "input"))
    )
    (net (code "44") (name "Net-(IC18A-VMON)") (class "Default")
      (node (ref "IC18") (pin "21") (pinfunction "VMON_21") (pintype "output"))
      (node (ref "R43") (pin "1") (pinfunction "1_1") (pintype "passive"))
    )
    (net (code "45") (name "Net-(IC18A-nGRST)") (class "Default")
      (node (ref "IC18") (pin "78") (pinfunction "nGRST_78") (pintype "input"))
      (node (ref "IC18") (pin "79") (pinfunction "nPOR_79") (pintype "input"))
      (node (ref "R28") (pin "1") (pinfunction "1_1") (pintype "passive"))
    )
    (net (code "46") (name "Net-(T1-D)") (class "Default")
      (node (ref "R30") (pin "1") (pinfunction "1_1") (pintype "passive"))
      (node (ref "T1") (pin "3") (pinfunction "D_3") (pintype "passive"))
    )
    (net (code "47") (name "unconnected-(IC18A-DBG_FSMI_0-Pad30)") (class "Default")
      (node (ref "IC18") (pin "30") (pinfunction "DBG_FSMI_0_30") (pintype "input+no_connect"))
    )
    (net (code "48") (name "unconnected-(IC18A-DBG_FSMI_1-Pad31)") (class "Default")
      (node (ref "IC18") (pin "31") (pinfunction "DBG_FSMI_1_31") (pintype "input+no_connect"))
    )
    (net (code "49") (name "unconnected-(IC18A-DBG_FSMI_2-Pad32)") (class "Default")
      (node (ref "IC18") (pin "32") (pinfunction "DBG_FSMI_2_32") (pintype "input+no_connect"))
    )
    (net (code "50") (name "unconnected-(IC18A-DBG_FSMO-Pad34)") (class "Default")
      (node (ref "IC18") (pin "34") (pinfunction "DBG_FSMO_34") (pintype "output+no_connect"))
    )
    (net (code "51") (name "unconnected-(IC18A-OUT_0_N-Pad65)") (class "Default")
      (node (ref "IC18") (pin "65") (pinfunction "OUT_0_N_65") (pintype "output+no_connect"))
    )
    (net (code "52") (name "unconnected-(IC18A-OUT_0_P-Pad66)") (class "Default")
      (node (ref "IC18") (pin "66") (pinfunction "OUT_0_P_66") (pintype "output+no_connect"))
    )
    (net (code "53") (name "unconnected-(IC18A-OUT_1_N-Pad63)") (class "Default")
      (node (ref "IC18") (pin "63") (pinfunction "OUT_1_N_63") (pintype "output+no_connect"))
    )
    (net (code "54") (name "unconnected-(IC18A-OUT_1_P-Pad64)") (class "Default")
      (node (ref "IC18") (pin "64") (pinfunction "OUT_1_P_64") (pintype "output+no_connect"))
    )
    (net (code "55") (name "unconnected-(IC18A-OUT_2_N-Pad61)") (class "Default")
      (node (ref "IC18") (pin "61") (pinfunction "OUT_2_N_61") (pintype "output+no_connect"))
    )
    (net (code "56") (name "unconnected-(IC18A-OUT_2_P-Pad62)") (class "Default")
      (node (ref "IC18") (pin "62") (pinfunction "OUT_2_P_62") (pintype "output+no_connect"))
    )
    (net (code "57") (name "unconnected-(IC18A-OUT_3_N-Pad59)") (class "Default")
      (node (ref "IC18") (pin "59") (pinfunction "OUT_3_N_59") (pintype "output+no_connect"))
    )
    (net (code "58") (name "unconnected-(IC18A-OUT_3_P-Pad60)") (class "Default")
      (node (ref "IC18") (pin "60") (pinfunction "OUT_3_P_60") (pintype "output+no_connect"))
    )
    (net (code "59") (name "unconnected-(IC18A-OUT_4_N-Pad56)") (class "Default")
      (node (ref "IC18") (pin "56") (pinfunction "OUT_4_N_56") (pintype "output+no_connect"))
    )
    (net (code "60") (name "unconnected-(IC18A-OUT_4_P-Pad57)") (class "Default")
      (node (ref "IC18") (pin "57") (pinfunction "OUT_4_P_57") (pintype "output+no_connect"))
    )
    (net (code "61") (name "unconnected-(IC18A-OUT_5_N-Pad54)") (class "Default")
      (node (ref "IC18") (pin "54") (pinfunction "OUT_5_N_54") (pintype "output+no_connect"))
    )
    (net (code "62") (name "unconnected-(IC18A-OUT_5_P-Pad55)") (class "Default")
      (node (ref "IC18") (pin "55") (pinfunction "OUT_5_P_55") (pintype "output+no_connect"))
    )
    (net (code "63") (name "unconnected-(IC18A-OUT_6_N-Pad52)") (class "Default")
      (node (ref "IC18") (pin "52") (pinfunction "OUT_6_N_52") (pintype "output+no_connect"))
    )
    (net (code "64") (name "unconnected-(IC18A-OUT_6_P-Pad53)") (class "Default")
      (node (ref "IC18") (pin "53") (pinfunction "OUT_6_P_53") (pintype "output+no_connect"))
    )
    (net (code "65") (name "unconnected-(IC18A-OUT_7_N-Pad50)") (class "Default")
      (node (ref "IC18") (pin "50") (pinfunction "OUT_7_N_50") (pintype "output+no_connect"))
    )
    (net (code "66") (name "unconnected-(IC18A-OUT_7_P-Pad51)") (class "Default")
      (node (ref "IC18") (pin "51") (pinfunction "OUT_7_P_51") (pintype "output+no_connect"))
    )
  )
)
